# Crimson_module.net
KiCad netlist of a schematic drawn in EAGLE
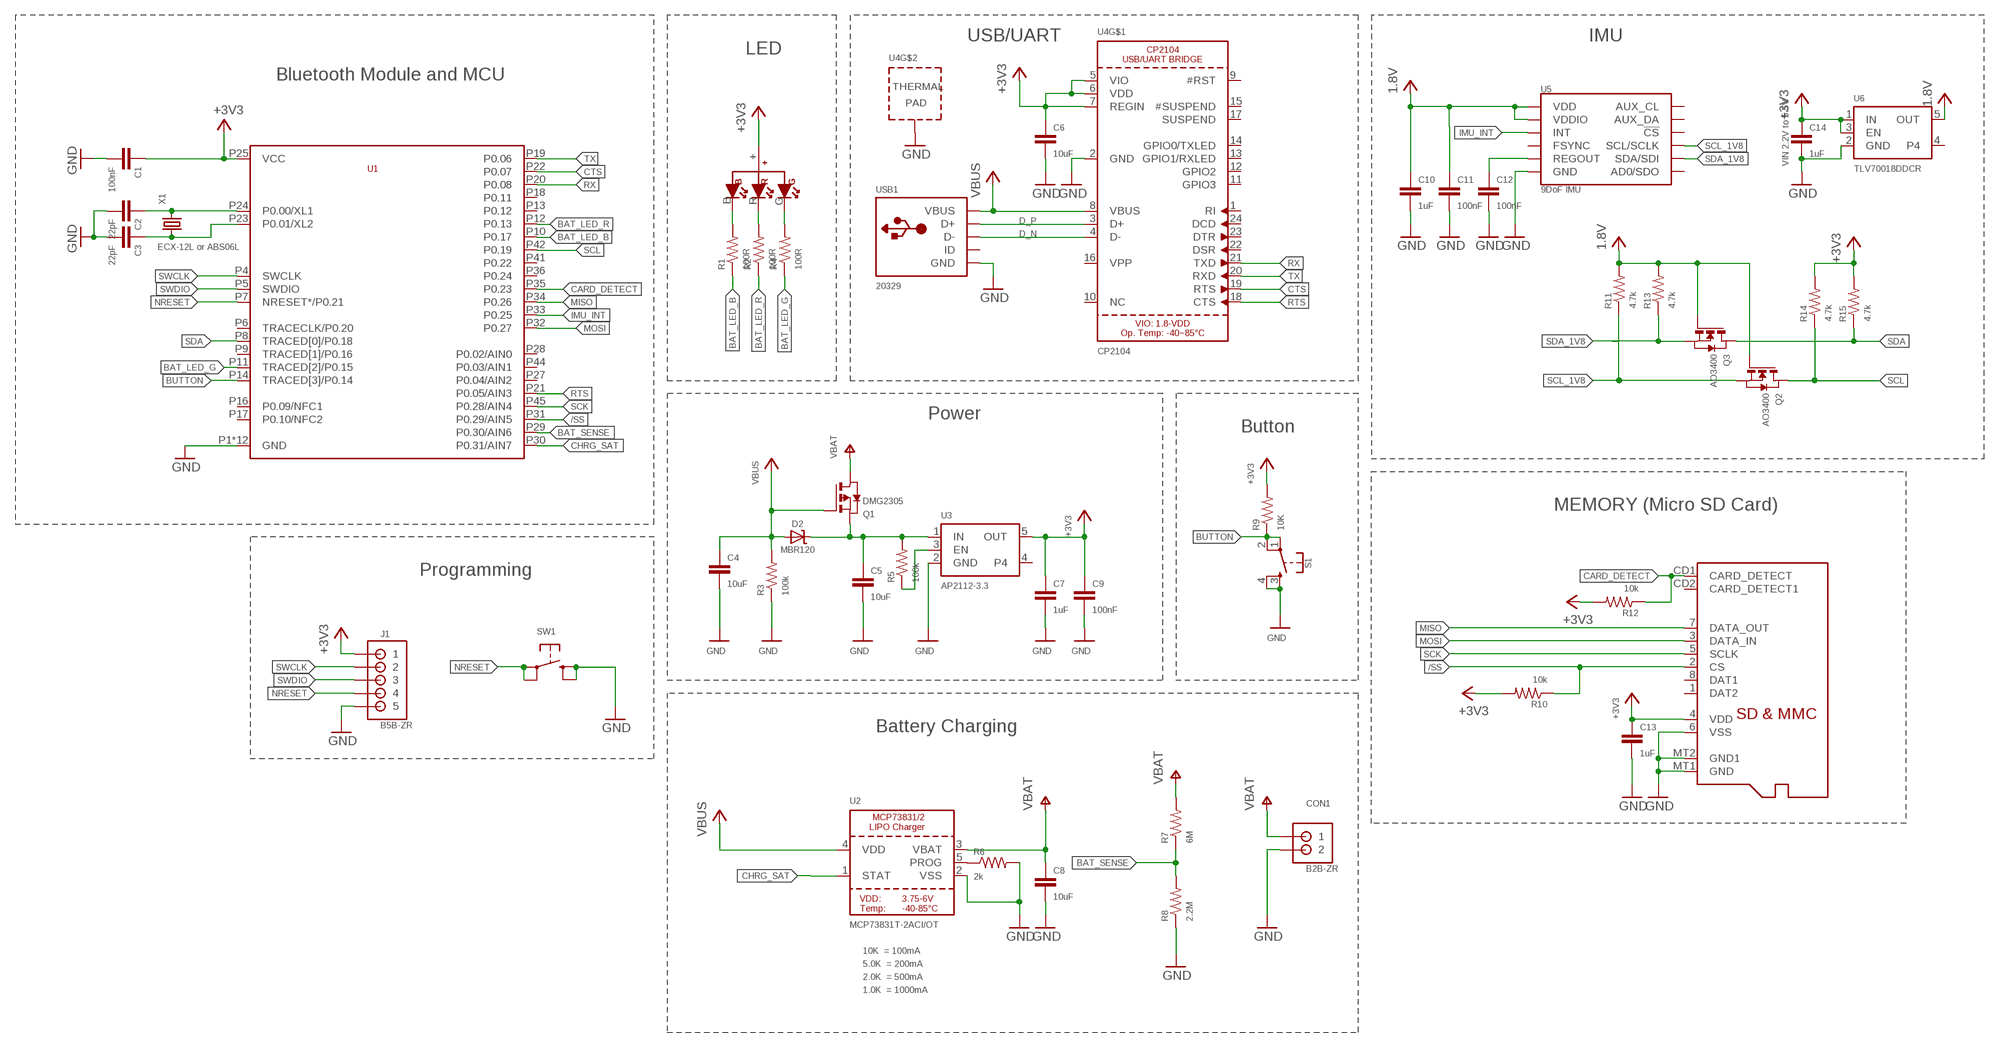
[diagram p0: schematic, sheet 1]

(export (version "E")
  (design (tool "Eeschema 10.0.6"))
  (components
    (comp (ref "C1")
      (value "100nF")
      (footprint "eagle-import:C0402")
      (libsource (lib "eagle-import") (part "C-EUC0402"))
    )
    (comp (ref "C2")
      (value "22pF")
      (footprint "eagle-import:C0402")
      (libsource (lib "eagle-import") (part "C-EUC0402"))
    )
    (comp (ref "C3")
      (value "22pF")
      (footprint "eagle-import:C0402")
      (libsource (lib "eagle-import") (part "C-EUC0402"))
    )
    (comp (ref "C4")
      (value "10uF")
      (footprint "eagle-import:C0402")
      (libsource (lib "eagle-import") (part "C-EUC0402"))
    )
    (comp (ref "C5")
      (value "10uF")
      (footprint "eagle-import:C0402")
      (libsource (lib "eagle-import") (part "C-EUC0402"))
    )
    (comp (ref "C6")
      (value "10uF")
      (footprint "eagle-import:C0402")
      (libsource (lib "eagle-import") (part "C-EUC0402"))
    )
    (comp (ref "C7")
      (value "1uF")
      (footprint "eagle-import:C0402")
      (libsource (lib "eagle-import") (part "C-EUC0402"))
    )
    (comp (ref "C8")
      (value "10uF")
      (footprint "eagle-import:C0402")
      (libsource (lib "eagle-import") (part "C-EUC0402"))
    )
    (comp (ref "C9")
      (value "100nF")
      (footprint "eagle-import:C0402")
      (libsource (lib "eagle-import") (part "C-EUC0402"))
    )
    (comp (ref "C10")
      (value "1uF")
      (footprint "eagle-import:C0402")
      (libsource (lib "eagle-import") (part "C-EUC0402"))
    )
    (comp (ref "C11")
      (value "100nF")
      (footprint "eagle-import:C0402")
      (libsource (lib "eagle-import") (part "C-EUC0402"))
    )
    (comp (ref "C12")
      (value "100nF")
      (footprint "eagle-import:C0402")
      (libsource (lib "eagle-import") (part "C-EUC0402"))
    )
    (comp (ref "C13")
      (value "1uF")
      (footprint "eagle-import:C0402")
      (libsource (lib "eagle-import") (part "C-EUC0402"))
    )
    (comp (ref "C14")
      (value "1uF")
      (footprint "eagle-import:C0402")
      (libsource (lib "eagle-import") (part "C-EUC0402"))
    )
    (comp (ref "CON1")
      (value "B2B-ZR")
      (footprint "eagle-import:B2B-ZR")
      (libsource (lib "eagle-import") (part "B2B-ZR"))
    )
    (comp (ref "D1")
      (value "B2020RGBA")
      (footprint "eagle-import:B2020RGBA")
      (libsource (lib "eagle-import") (part "B2020RGBA"))
    )
    (comp (ref "D2")
      (value "MBR120")
      (footprint "eagle-import:SOD-123")
      (libsource (lib "eagle-import") (part "DIODE-SCHOTTKYSOD-123"))
    )
    (comp (ref "J1")
      (value "B5B-ZR")
      (footprint "eagle-import:B5B-ZR")
      (libsource (lib "eagle-import") (part "B5B-ZR"))
    )
    (comp (ref "Q1")
      (value "DMG2305")
      (footprint "eagle-import:SOT-23")
      (libsource (lib "eagle-import") (part "PMOS-SOT23"))
    )
    (comp (ref "Q2")
      (value "AO3400")
      (footprint "eagle-import:SOT-23")
      (libsource (lib "eagle-import") (part "NMOS-SOT23"))
    )
    (comp (ref "Q3")
      (value "AO3400")
      (footprint "eagle-import:SOT-23")
      (libsource (lib "eagle-import") (part "NMOS-SOT23"))
    )
    (comp (ref "R1")
      (value "100R")
      (footprint "eagle-import:R0402")
      (libsource (lib "eagle-import") (part "R-US_R0402"))
    )
    (comp (ref "R2")
      (value "100R")
      (footprint "eagle-import:R0402")
      (libsource (lib "eagle-import") (part "R-US_R0402"))
    )
    (comp (ref "R3")
      (value "100k")
      (footprint "eagle-import:R0402")
      (libsource (lib "eagle-import") (part "R-US_R0402"))
    )
    (comp (ref "R4")
      (value "100R")
      (footprint "eagle-import:R0402")
      (libsource (lib "eagle-import") (part "R-US_R0402"))
    )
    (comp (ref "R5")
      (value "100k")
      (footprint "eagle-import:R0402")
      (libsource (lib "eagle-import") (part "R-US_R0402"))
    )
    (comp (ref "R6")
      (value "2k")
      (footprint "eagle-import:R0402")
      (libsource (lib "eagle-import") (part "R-US_R0402"))
    )
    (comp (ref "R7")
      (value "6M")
      (footprint "eagle-import:R0402")
      (libsource (lib "eagle-import") (part "R-US_R0402"))
    )
    (comp (ref "R8")
      (value "2.2M")
      (footprint "eagle-import:R0402")
      (libsource (lib "eagle-import") (part "R-US_R0402"))
    )
    (comp (ref "R9")
      (value "10K")
      (footprint "eagle-import:R0402")
      (libsource (lib "eagle-import") (part "R-US_R0402"))
    )
    (comp (ref "R10")
      (value "10k")
      (footprint "eagle-import:R0402")
      (libsource (lib "eagle-import") (part "R-US_R0402"))
    )
    (comp (ref "R11")
      (value "4.7k")
      (footprint "eagle-import:R0402")
      (libsource (lib "eagle-import") (part "R-US_R0402"))
    )
    (comp (ref "R12")
      (value "10k")
      (footprint "eagle-import:R0402")
      (libsource (lib "eagle-import") (part "R-US_R0402"))
    )
    (comp (ref "R13")
      (value "4.7k")
      (footprint "eagle-import:R0402")
      (libsource (lib "eagle-import") (part "R-US_R0402"))
    )
    (comp (ref "R14")
      (value "4.7k")
      (footprint "eagle-import:R0402")
      (libsource (lib "eagle-import") (part "R-US_R0402"))
    )
    (comp (ref "R15")
      (value "4.7k")
      (footprint "eagle-import:R0402")
      (libsource (lib "eagle-import") (part "R-US_R0402"))
    )
    (comp (ref "S1")
      (value "MOMENTARY-SWITCH-SPST-2-SMD-5.2MM")
      (footprint "eagle-import:TACTILE_SWITCH_SMD_5.2MM")
      (libsource (lib "eagle-import") (part "MOMENTARY-SWITCH-SPST-2-SMD-5.2MM"))
    )
    (comp (ref "SD1")
      (value "MICROSD")
      (footprint "eagle-import:MICROSD")
      (libsource (lib "eagle-import") (part "MICROSD"))
    )
    (comp (ref "SW1")
      (value "MICROBUILDER_SWITCH_TACT_SMT4.6X2.8")
      (footprint "eagle-import:MICROBUILDER_BTN_KMR2_4.6X2.8")
      (libsource (lib "eagle-import") (part "MICROBUILDER_SWITCH_TACT_SMT4.6X2.8"))
    )
    (comp (ref "U1")
      (value "BMD-350")
      (footprint "eagle-import:BMD-350")
      (libsource (lib "eagle-import") (part "BMD-350"))
    )
    (comp (ref "U2")
      (value "MCP73831T-2ACI/OT")
      (footprint "eagle-import:SOT23-5")
      (libsource (lib "eagle-import") (part "MCP73831/2"))
    )
    (comp (ref "U3")
      (value "AP2112-3.3")
      (footprint "eagle-import:SOT23-5")
      (libsource (lib "eagle-import") (part "VREG_SOT23-5"))
    )
    (comp (ref "U4")
      (value "CP2104")
      (footprint "eagle-import:QFN24_4MM_SMSC")
      (libsource (lib "eagle-import") (part "CP2104"))
    )
    (comp (ref "U5")
      (value "9DoF IMU")
      (footprint "eagle-import:QFN24-3X3")
      (libsource (lib "eagle-import") (part "ICM-20948"))
    )
    (comp (ref "U6")
      (value "TLV70018DDCR")
      (footprint "eagle-import:MICROBUILDER_SOT23-5")
      (libsource (lib "eagle-import") (part "MICROBUILDER_VREG_SOT23-5"))
    )
    (comp (ref "USB1")
      (value "20329")
      (footprint "eagle-import:4UCONN_20329_V2")
      (libsource (lib "eagle-import") (part "USB_MICRO_20329_V2"))
    )
    (comp (ref "X1")
      (value "ECX-12L or ABS06L")
      (footprint "eagle-import:2.0X1.2")
      (libsource (lib "eagle-import") (part "KX-327-RT"))
    )
  )
  (nets
    (net (code "1") (name "+3V3") (class "Default")
      (node (ref "C1") (pin "1") (pinfunction "1_1") (pintype "passive"))
      (node (ref "C13") (pin "1") (pinfunction "1_1") (pintype "passive"))
      (node (ref "C14") (pin "1") (pinfunction "1_1") (pintype "passive"))
      (node (ref "C6") (pin "1") (pinfunction "1_1") (pintype "passive"))
      (node (ref "C7") (pin "1") (pinfunction "1_1") (pintype "passive"))
      (node (ref "C9") (pin "1") (pinfunction "1_1") (pintype "passive"))
      (node (ref "D1") (pin "+") (pinfunction "+_+") (pintype "bidirectional"))
      (node (ref "J1") (pin "1") (pinfunction "1_1") (pintype "bidirectional"))
      (node (ref "R10") (pin "2") (pinfunction "2_2") (pintype "passive"))
      (node (ref "R12") (pin "2") (pinfunction "2_2") (pintype "passive"))
      (node (ref "R14") (pin "2") (pinfunction "2_2") (pintype "passive"))
      (node (ref "R15") (pin "2") (pinfunction "2_2") (pintype "passive"))
      (node (ref "R9") (pin "2") (pinfunction "2_2") (pintype "passive"))
      (node (ref "SD1") (pin "4") (pinfunction "VDD_4") (pintype "power_in"))
      (node (ref "U1") (pin "P25") (pinfunction "VCC_P25") (pintype "bidirectional"))
      (node (ref "U3") (pin "5") (pinfunction "OUT_5") (pintype "power_in"))
      (node (ref "U4") (pin "5") (pinfunction "VIO_5") (pintype "power_in"))
      (node (ref "U4") (pin "6") (pinfunction "VDD_6") (pintype "power_in"))
      (node (ref "U4") (pin "7") (pinfunction "REGIN_7") (pintype "power_in"))
      (node (ref "U6") (pin "1") (pinfunction "IN_1") (pintype "power_in"))
      (node (ref "U6") (pin "3") (pinfunction "EN_3") (pintype "input"))
    )
    (net (code "2") (name "/D_N") (class "Default")
      (node (ref "U4") (pin "4") (pinfunction "D-_4") (pintype "bidirectional"))
      (node (ref "USB1") (pin "D-") (pinfunction "D-_D-") (pintype "bidirectional"))
    )
    (net (code "3") (name "/D_P") (class "Default")
      (node (ref "U4") (pin "3") (pinfunction "D+_3") (pintype "bidirectional"))
      (node (ref "USB1") (pin "D+") (pinfunction "D+_D+") (pintype "bidirectional"))
    )
    (net (code "4") (name "1.8V") (class "Default")
      (node (ref "C10") (pin "1") (pinfunction "1_1") (pintype "passive"))
      (node (ref "C11") (pin "1") (pinfunction "1_1") (pintype "passive"))
      (node (ref "Q2") (pin "G") (pinfunction "G_G") (pintype "passive"))
      (node (ref "Q3") (pin "G") (pinfunction "G_G") (pintype "passive"))
      (node (ref "R11") (pin "2") (pinfunction "2_2") (pintype "passive"))
      (node (ref "R13") (pin "2") (pinfunction "2_2") (pintype "passive"))
      (node (ref "U5") (pin "13") (pinfunction "VDD_13") (pintype "bidirectional"))
      (node (ref "U5") (pin "8") (pinfunction "VDDIO_8") (pintype "bidirectional"))
      (node (ref "U6") (pin "5") (pinfunction "OUT_5") (pintype "power_in"))
    )
    (net (code "5") (name "BAT_LED_B") (class "Default")
      (node (ref "R1") (pin "1") (pinfunction "1_1") (pintype "passive"))
      (node (ref "U1") (pin "P10") (pinfunction "P0.17_P10") (pintype "bidirectional"))
    )
    (net (code "6") (name "BAT_LED_G") (class "Default")
      (node (ref "R4") (pin "1") (pinfunction "1_1") (pintype "passive"))
      (node (ref "U1") (pin "P11") (pinfunction "TRACED[2]/P0.15_P11") (pintype "bidirectional"))
    )
    (net (code "7") (name "BAT_LED_R") (class "Default")
      (node (ref "R2") (pin "1") (pinfunction "1_1") (pintype "passive"))
      (node (ref "U1") (pin "P12") (pinfunction "P0.13_P12") (pintype "bidirectional"))
    )
    (net (code "8") (name "BAT_SENSE") (class "Default")
      (node (ref "R7") (pin "1") (pinfunction "1_1") (pintype "passive"))
      (node (ref "R8") (pin "2") (pinfunction "2_2") (pintype "passive"))
      (node (ref "U1") (pin "P29") (pinfunction "P0.30/AIN6_P29") (pintype "bidirectional"))
    )
    (net (code "9") (name "BUTTON") (class "Default")
      (node (ref "R9") (pin "1") (pinfunction "1_1") (pintype "passive"))
      (node (ref "S1") (pin "1") (pinfunction "1_1") (pintype "passive"))
      (node (ref "S1") (pin "2") (pinfunction "2_2") (pintype "passive"))
      (node (ref "U1") (pin "P14") (pinfunction "TRACED[3]/P0.14_P14") (pintype "bidirectional"))
    )
    (net (code "10") (name "CARD_DETECT") (class "Default")
      (node (ref "R12") (pin "1") (pinfunction "1_1") (pintype "passive"))
      (node (ref "SD1") (pin "CD1") (pinfunction "CARD_DETECT_CD1") (pintype "passive"))
      (node (ref "U1") (pin "P35") (pinfunction "P0.23_P35") (pintype "bidirectional"))
    )
    (net (code "11") (name "CHRG_SAT") (class "Default")
      (node (ref "U1") (pin "P30") (pinfunction "P0.31/AIN7_P30") (pintype "bidirectional"))
      (node (ref "U2") (pin "1") (pinfunction "STAT_1") (pintype "output"))
    )
    (net (code "12") (name "CTS") (class "Default")
      (node (ref "U1") (pin "P22") (pinfunction "P0.07_P22") (pintype "bidirectional"))
      (node (ref "U4") (pin "19") (pinfunction "RTS_19") (pintype "output"))
    )
    (net (code "13") (name "GND") (class "Default")
      (node (ref "C1") (pin "2") (pinfunction "2_2") (pintype "passive"))
      (node (ref "C10") (pin "2") (pinfunction "2_2") (pintype "passive"))
      (node (ref "C11") (pin "2") (pinfunction "2_2") (pintype "passive"))
      (node (ref "C12") (pin "2") (pinfunction "2_2") (pintype "passive"))
      (node (ref "C13") (pin "2") (pinfunction "2_2") (pintype "passive"))
      (node (ref "C14") (pin "2") (pinfunction "2_2") (pintype "passive"))
      (node (ref "C2") (pin "2") (pinfunction "2_2") (pintype "passive"))
      (node (ref "C3") (pin "2") (pinfunction "2_2") (pintype "passive"))
      (node (ref "C4") (pin "2") (pinfunction "2_2") (pintype "passive"))
      (node (ref "C5") (pin "2") (pinfunction "2_2") (pintype "passive"))
      (node (ref "C6") (pin "2") (pinfunction "2_2") (pintype "passive"))
      (node (ref "C7") (pin "2") (pinfunction "2_2") (pintype "passive"))
      (node (ref "C8") (pin "2") (pinfunction "2_2") (pintype "passive"))
      (node (ref "C9") (pin "2") (pinfunction "2_2") (pintype "passive"))
      (node (ref "CON1") (pin "2") (pinfunction "2_2") (pintype "bidirectional"))
      (node (ref "J1") (pin "5") (pinfunction "5_5") (pintype "bidirectional"))
      (node (ref "R3") (pin "1") (pinfunction "1_1") (pintype "passive"))
      (node (ref "R6") (pin "2") (pinfunction "2_2") (pintype "passive"))
      (node (ref "R8") (pin "1") (pinfunction "1_1") (pintype "passive"))
      (node (ref "S1") (pin "3") (pinfunction "3_3") (pintype "passive"))
      (node (ref "S1") (pin "4") (pinfunction "4_4") (pintype "passive"))
      (node (ref "SD1") (pin "6") (pinfunction "VSS_6") (pintype "power_in"))
      (node (ref "SD1") (pin "MT1") (pinfunction "GND_MT1") (pintype "power_in"))
      (node (ref "SD1") (pin "MT2") (pinfunction "GND1_MT2") (pintype "power_in"))
      (node (ref "SW1") (pin "B") (pinfunction "S_B") (pintype "passive"))
      (node (ref "SW1") (pin "B'") (pinfunction "S1_B'") (pintype "passive"))
      (node (ref "U1") (pin "P1") (pinfunction "GND_P1") (pintype "bidirectional"))
      (node (ref "U1") (pin "P15") (pinfunction "GND_P15") (pintype "bidirectional"))
      (node (ref "U1") (pin "P2") (pinfunction "GND_P2") (pintype "bidirectional"))
      (node (ref "U1") (pin "P26") (pinfunction "GND_P26") (pintype "bidirectional"))
      (node (ref "U1") (pin "P3") (pinfunction "GND_P3") (pintype "bidirectional"))
      (node (ref "U1") (pin "P37") (pinfunction "GND_P37") (pintype "bidirectional"))
      (node (ref "U1") (pin "P38") (pinfunction "GND_P38") (pintype "bidirectional"))
      (node (ref "U1") (pin "P39") (pinfunction "GND_P39") (pintype "bidirectional"))
      (node (ref "U1") (pin "P40") (pinfunction "GND_P40") (pintype "bidirectional"))
      (node (ref "U1") (pin "P43") (pinfunction "GND_P43") (pintype "bidirectional"))
      (node (ref "U1") (pin "P46") (pinfunction "GND_P46") (pintype "bidirectional"))
      (node (ref "U1") (pin "P47") (pinfunction "GND_P47") (pintype "bidirectional"))
      (node (ref "U2") (pin "2") (pinfunction "VSS_2") (pintype "power_in"))
      (node (ref "U3") (pin "2") (pinfunction "GND_2") (pintype "power_in"))
      (node (ref "U4") (pin "2") (pinfunction "GND_2") (pintype "power_in"))
      (node (ref "U4") (pin "THERM") (pinfunction "TP_THERM") (pintype "power_in"))
      (node (ref "U5") (pin "18") (pinfunction "GND_18") (pintype "bidirectional"))
      (node (ref "U5") (pin "20") (pinfunction "GND_20") (pintype "bidirectional"))
      (node (ref "U6") (pin "2") (pinfunction "GND_2") (pintype "power_in"))
      (node (ref "USB1") (pin "BASE@1") (pinfunction "GND_BASE@1") (pintype "power_in"))
      (node (ref "USB1") (pin "BASE@2") (pinfunction "GND_BASE@2") (pintype "power_in"))
      (node (ref "USB1") (pin "GND") (pinfunction "GND_GND") (pintype "power_in"))
      (node (ref "USB1") (pin "SPRT@1") (pinfunction "GND_SPRT@1") (pintype "power_in"))
      (node (ref "USB1") (pin "SPRT@2") (pinfunction "GND_SPRT@2") (pintype "power_in"))
      (node (ref "USB1") (pin "SPRT@3") (pinfunction "GND_SPRT@3") (pintype "power_in"))
      (node (ref "USB1") (pin "SPRT@4") (pinfunction "GND_SPRT@4") (pintype "power_in"))
    )
    (net (code "14") (name "IMU_INT") (class "Default")
      (node (ref "U1") (pin "P33") (pinfunction "P0.25_P33") (pintype "bidirectional"))
      (node (ref "U5") (pin "12") (pinfunction "INT_12") (pintype "bidirectional"))
    )
    (net (code "15") (name "MISO") (class "Default")
      (node (ref "SD1") (pin "7") (pinfunction "DATA_OUT_7") (pintype "output"))
      (node (ref "U1") (pin "P34") (pinfunction "P0.26_P34") (pintype "bidirectional"))
    )
    (net (code "16") (name "MOSI") (class "Default")
      (node (ref "SD1") (pin "3") (pinfunction "DATA_IN_3") (pintype "input"))
      (node (ref "U1") (pin "P32") (pinfunction "P0.27_P32") (pintype "bidirectional"))
    )
    (net (code "17") (name "NRESET") (class "Default")
      (node (ref "J1") (pin "4") (pinfunction "4_4") (pintype "bidirectional"))
      (node (ref "SW1") (pin "A") (pinfunction "P_A") (pintype "passive"))
      (node (ref "SW1") (pin "A'") (pinfunction "P1_A'") (pintype "passive"))
      (node (ref "U1") (pin "P7") (pinfunction "NRESET*/P0.21_P7") (pintype "bidirectional"))
    )
    (net (code "18") (name "Net-(D1-PadB)") (class "Default")
      (node (ref "D1") (pin "B") (pinfunction "B_B") (pintype "bidirectional"))
      (node (ref "R1") (pin "2") (pinfunction "2_2") (pintype "passive"))
    )
    (net (code "19") (name "Net-(D1-PadG)") (class "Default")
      (node (ref "D1") (pin "G") (pinfunction "G_G") (pintype "bidirectional"))
      (node (ref "R4") (pin "2") (pinfunction "2_2") (pintype "passive"))
    )
    (net (code "20") (name "Net-(D1-PadR)") (class "Default")
      (node (ref "D1") (pin "R") (pinfunction "R_R") (pintype "bidirectional"))
      (node (ref "R2") (pin "2") (pinfunction "2_2") (pintype "passive"))
    )
    (net (code "21") (name "Net-(U1-P0.00{slash}XL1)") (class "Default")
      (node (ref "C2") (pin "1") (pinfunction "1_1") (pintype "passive"))
      (node (ref "U1") (pin "P24") (pinfunction "P0.00/XL1_P24") (pintype "bidirectional"))
      (node (ref "X1") (pin "2") (pinfunction "2_2") (pintype "passive"))
    )
    (net (code "22") (name "Net-(U1-P0.01{slash}XL2)") (class "Default")
      (node (ref "C3") (pin "1") (pinfunction "1_1") (pintype "passive"))
      (node (ref "U1") (pin "P23") (pinfunction "P0.01/XL2_P23") (pintype "bidirectional"))
      (node (ref "X1") (pin "1") (pinfunction "1_1") (pintype "passive"))
    )
    (net (code "23") (name "Net-(U2-PROG)") (class "Default")
      (node (ref "R6") (pin "1") (pinfunction "1_1") (pintype "passive"))
      (node (ref "U2") (pin "5") (pinfunction "PROG_5") (pintype "input"))
    )
    (net (code "24") (name "Net-(U3-EN)") (class "Default")
      (node (ref "R5") (pin "1") (pinfunction "1_1") (pintype "passive"))
      (node (ref "U3") (pin "3") (pinfunction "EN_3") (pintype "input"))
    )
    (net (code "25") (name "Net-(U3-IN)") (class "Default")
      (node (ref "C5") (pin "1") (pinfunction "1_1") (pintype "passive"))
      (node (ref "D2") (pin "C") (pinfunction "C_C") (pintype "passive"))
      (node (ref "Q1") (pin "S") (pinfunction "S_S") (pintype "passive"))
      (node (ref "R5") (pin "2") (pinfunction "2_2") (pintype "passive"))
      (node (ref "U3") (pin "1") (pinfunction "IN_1") (pintype "power_in"))
    )
    (net (code "26") (name "Net-(U5-REGOUT)") (class "Default")
      (node (ref "C12") (pin "1") (pinfunction "1_1") (pintype "passive"))
      (node (ref "U5") (pin "10") (pinfunction "REGOUT_10") (pintype "bidirectional"))
    )
    (net (code "27") (name "RTS") (class "Default")
      (node (ref "U1") (pin "P21") (pinfunction "P0.05/AIN3_P21") (pintype "bidirectional"))
      (node (ref "U4") (pin "18") (pinfunction "CTS_18") (pintype "input"))
    )
    (net (code "28") (name "RX") (class "Default")
      (node (ref "U1") (pin "P20") (pinfunction "P0.08_P20") (pintype "bidirectional"))
      (node (ref "U4") (pin "21") (pinfunction "TXD_21") (pintype "output"))
    )
    (net (code "29") (name "SCK") (class "Default")
      (node (ref "SD1") (pin "5") (pinfunction "SCLK_5") (pintype "input"))
      (node (ref "U1") (pin "P45") (pinfunction "P0.28/AIN4_P45") (pintype "bidirectional"))
    )
    (net (code "30") (name "SCL") (class "Default")
      (node (ref "Q2") (pin "D") (pinfunction "D_D") (pintype "passive"))
      (node (ref "R14") (pin "1") (pinfunction "1_1") (pintype "passive"))
      (node (ref "U1") (pin "P42") (pinfunction "P0.19_P42") (pintype "bidirectional"))
    )
    (net (code "31") (name "SCL_1V8") (class "Default")
      (node (ref "Q2") (pin "S") (pinfunction "S_S") (pintype "passive"))
      (node (ref "R11") (pin "1") (pinfunction "1_1") (pintype "passive"))
      (node (ref "U5") (pin "23") (pinfunction "SCL/SCLK_23") (pintype "bidirectional"))
    )
    (net (code "32") (name "SDA") (class "Default")
      (node (ref "Q3") (pin "D") (pinfunction "D_D") (pintype "passive"))
      (node (ref "R15") (pin "1") (pinfunction "1_1") (pintype "passive"))
      (node (ref "U1") (pin "P8") (pinfunction "TRACED[0]/P0.18_P8") (pintype "bidirectional"))
    )
    (net (code "33") (name "SDA_1V8") (class "Default")
      (node (ref "Q3") (pin "S") (pinfunction "S_S") (pintype "passive"))
      (node (ref "R13") (pin "1") (pinfunction "1_1") (pintype "passive"))
      (node (ref "U5") (pin "24") (pinfunction "SDA/SDI_24") (pintype "bidirectional"))
    )
    (net (code "34") (name "SWCLK") (class "Default")
      (node (ref "J1") (pin "2") (pinfunction "2_2") (pintype "bidirectional"))
      (node (ref "U1") (pin "P4") (pinfunction "SWCLK_P4") (pintype "bidirectional"))
    )
    (net (code "35") (name "SWDIO") (class "Default")
      (node (ref "J1") (pin "3") (pinfunction "3_3") (pintype "bidirectional"))
      (node (ref "U1") (pin "P5") (pinfunction "SWDIO_P5") (pintype "bidirectional"))
    )
    (net (code "36") (name "TX") (class "Default")
      (node (ref "U1") (pin "P19") (pinfunction "P0.06_P19") (pintype "bidirectional"))
      (node (ref "U4") (pin "20") (pinfunction "RXD_20") (pintype "input"))
    )
    (net (code "37") (name "VBAT") (class "Default")
      (node (ref "C8") (pin "1") (pinfunction "1_1") (pintype "passive"))
      (node (ref "CON1") (pin "1") (pinfunction "1_1") (pintype "bidirectional"))
      (node (ref "Q1") (pin "D") (pinfunction "D_D") (pintype "passive"))
      (node (ref "R7") (pin "2") (pinfunction "2_2") (pintype "passive"))
      (node (ref "U2") (pin "3") (pinfunction "VBAT_3") (pintype "power_in"))
    )
    (net (code "38") (name "VBUS") (class "Default")
      (node (ref "C4") (pin "1") (pinfunction "1_1") (pintype "passive"))
      (node (ref "D2") (pin "A") (pinfunction "A_A") (pintype "passive"))
      (node (ref "Q1") (pin "G") (pinfunction "G_G") (pintype "passive"))
      (node (ref "R3") (pin "2") (pinfunction "2_2") (pintype "passive"))
      (node (ref "U2") (pin "4") (pinfunction "VDD_4") (pintype "power_in"))
      (node (ref "U4") (pin "8") (pinfunction "VBUS_8") (pintype "power_in"))
      (node (ref "USB1") (pin "VBUS") (pinfunction "VBUS_VBUS") (pintype "power_in"))
    )
    (net (code "39") (name "unconnected-(SD1-CARD_DETECT1-PadCD2)") (class "Default")
      (node (ref "SD1") (pin "CD2") (pinfunction "CARD_DETECT1_CD2") (pintype "passive"))
    )
    (net (code "40") (name "unconnected-(SD1-DAT1-Pad8)") (class "Default")
      (node (ref "SD1") (pin "8") (pinfunction "DAT1_8") (pintype "bidirectional"))
    )
    (net (code "41") (name "unconnected-(SD1-DAT2-Pad1)") (class "Default")
      (node (ref "SD1") (pin "1") (pinfunction "DAT2_1") (pintype "bidirectional"))
    )
    (net (code "42") (name "unconnected-(U1-P0.02{slash}AIN0-PadP28)") (class "Default")
      (node (ref "U1") (pin "P28") (pinfunction "P0.02/AIN0_P28") (pintype "bidirectional"))
    )
    (net (code "43") (name "unconnected-(U1-P0.03{slash}AIN1-PadP44)") (class "Default")
      (node (ref "U1") (pin "P44") (pinfunction "P0.03/AIN1_P44") (pintype "bidirectional"))
    )
    (net (code "44") (name "unconnected-(U1-P0.04{slash}AIN2-PadP27)") (class "Default")
      (node (ref "U1") (pin "P27") (pinfunction "P0.04/AIN2_P27") (pintype "bidirectional"))
    )
    (net (code "45") (name "unconnected-(U1-P0.09{slash}NFC1-PadP16)") (class "Default")
      (node (ref "U1") (pin "P16") (pinfunction "P0.09/NFC1_P16") (pintype "bidirectional"))
    )
    (net (code "46") (name "unconnected-(U1-P0.10{slash}NFC2-PadP17)") (class "Default")
      (node (ref "U1") (pin "P17") (pinfunction "P0.10/NFC2_P17") (pintype "bidirectional"))
    )
    (net (code "47") (name "unconnected-(U1-P0.11-PadP18)") (class "Default")
      (node (ref "U1") (pin "P18") (pinfunction "P0.11_P18") (pintype "bidirectional"))
    )
    (net (code "48") (name "unconnected-(U1-P0.12-PadP13)") (class "Default")
      (node (ref "U1") (pin "P13") (pinfunction "P0.12_P13") (pintype "bidirectional"))
    )
    (net (code "49") (name "unconnected-(U1-P0.22-PadP41)") (class "Default")
      (node (ref "U1") (pin "P41") (pinfunction "P0.22_P41") (pintype "bidirectional"))
    )
    (net (code "50") (name "unconnected-(U1-P0.24-PadP36)") (class "Default")
      (node (ref "U1") (pin "P36") (pinfunction "P0.24_P36") (pintype "bidirectional"))
    )
    (net (code "51") (name "unconnected-(U1-TRACECLK{slash}P0.20-PadP6)") (class "Default")
      (node (ref "U1") (pin "P6") (pinfunction "TRACECLK/P0.20_P6") (pintype "bidirectional"))
    )
    (net (code "52") (name "unconnected-(U1-TRACED[1]{slash}P0.16-PadP9)") (class "Default")
      (node (ref "U1") (pin "P9") (pinfunction "TRACED[1]/P0.16_P9") (pintype "bidirectional"))
    )
    (net (code "53") (name "unconnected-(U3-P4-Pad4)") (class "Default")
      (node (ref "U3") (pin "4") (pinfunction "P4_4") (pintype "bidirectional"))
    )
    (net (code "54") (name "unconnected-(U4A-#RST-Pad9)") (class "Default")
      (node (ref "U4") (pin "9") (pinfunction "#RST_9") (pintype "bidirectional"))
    )
    (net (code "55") (name "unconnected-(U4A-#SUSPEND-Pad15)") (class "Default")
      (node (ref "U4") (pin "15") (pinfunction "#SUSPEND_15") (pintype "output"))
    )
    (net (code "56") (name "unconnected-(U4A-DCD-Pad24)") (class "Default")
      (node (ref "U4") (pin "24") (pinfunction "DCD_24") (pintype "input"))
    )
    (net (code "57") (name "unconnected-(U4A-DSR-Pad22)") (class "Default")
      (node (ref "U4") (pin "22") (pinfunction "DSR_22") (pintype "input"))
    )
    (net (code "58") (name "unconnected-(U4A-DTR-Pad23)") (class "Default")
      (node (ref "U4") (pin "23") (pinfunction "DTR_23") (pintype "output"))
    )
    (net (code "59") (name "unconnected-(U4A-GPIO0{slash}TXLED-Pad14)") (class "Default")
      (node (ref "U4") (pin "14") (pinfunction "GPIO0/TXLED_14") (pintype "bidirectional"))
    )
    (net (code "60") (name "unconnected-(U4A-GPIO1{slash}RXLED-Pad13)") (class "Default")
      (node (ref "U4") (pin "13") (pinfunction "GPIO1/RXLED_13") (pintype "bidirectional"))
    )
    (net (code "61") (name "unconnected-(U4A-GPIO2-Pad12)") (class "Default")
      (node (ref "U4") (pin "12") (pinfunction "GPIO2_12") (pintype "bidirectional"))
    )
    (net (code "62") (name "unconnected-(U4A-GPIO3-Pad11)") (class "Default")
      (node (ref "U4") (pin "11") (pinfunction "GPIO3_11") (pintype "bidirectional"))
    )
    (net (code "63") (name "unconnected-(U4A-NC-Pad10)") (class "Default")
      (node (ref "U4") (pin "10") (pinfunction "NC_10") (pintype "no_connect"))
    )
    (net (code "64") (name "unconnected-(U4A-RI-Pad1)") (class "Default")
      (node (ref "U4") (pin "1") (pinfunction "RI_1") (pintype "input"))
    )
    (net (code "65") (name "unconnected-(U4A-SUSPEND-Pad17)") (class "Default")
      (node (ref "U4") (pin "17") (pinfunction "SUSPEND_17") (pintype "output"))
    )
    (net (code "66") (name "unconnected-(U4A-VPP-Pad16)") (class "Default")
      (node (ref "U4") (pin "16") (pinfunction "VPP_16") (pintype "bidirectional"))
    )
    (net (code "67") (name "unconnected-(U5-AD0{slash}SDO-Pad9)") (class "Default")
      (node (ref "U5") (pin "9") (pinfunction "AD0/SDO_9") (pintype "bidirectional"))
    )
    (net (code "68") (name "unconnected-(U5-AUX_CL-Pad7)") (class "Default")
      (node (ref "U5") (pin "7") (pinfunction "AUX_CL_7") (pintype "bidirectional"))
    )
    (net (code "69") (name "unconnected-(U5-AUX_DA-Pad21)") (class "Default")
      (node (ref "U5") (pin "21") (pinfunction "AUX_DA_21") (pintype "bidirectional"))
    )
    (net (code "70") (name "unconnected-(U5-FSYNC-Pad11)") (class "Default")
      (node (ref "U5") (pin "11") (pinfunction "FSYNC_11") (pintype "bidirectional"))
    )
    (net (code "71") (name "unconnected-(U5-~{CS}-Pad22)") (class "Default")
      (node (ref "U5") (pin "22") (pinfunction "~{CS}_22") (pintype "bidirectional"))
    )
    (net (code "72") (name "unconnected-(U6-P4-Pad4)") (class "Default")
      (node (ref "U6") (pin "4") (pinfunction "P4_4") (pintype "bidirectional"))
    )
    (net (code "73") (name "unconnected-(USB1-PadID)") (class "Default")
      (node (ref "USB1") (pin "ID") (pinfunction "ID_ID") (pintype "bidirectional"))
    )
    (net (code "74") (name "{slash}SS") (class "Default")
      (node (ref "R10") (pin "1") (pinfunction "1_1") (pintype "passive"))
      (node (ref "SD1") (pin "2") (pinfunction "CS_2") (pintype "input"))
      (node (ref "U1") (pin "P31") (pinfunction "P0.29/AIN5_P31") (pintype "bidirectional"))
    )
  )
)
